# 01_MAIN.net
KiCad netlist of a schematic drawn in Altium Designer
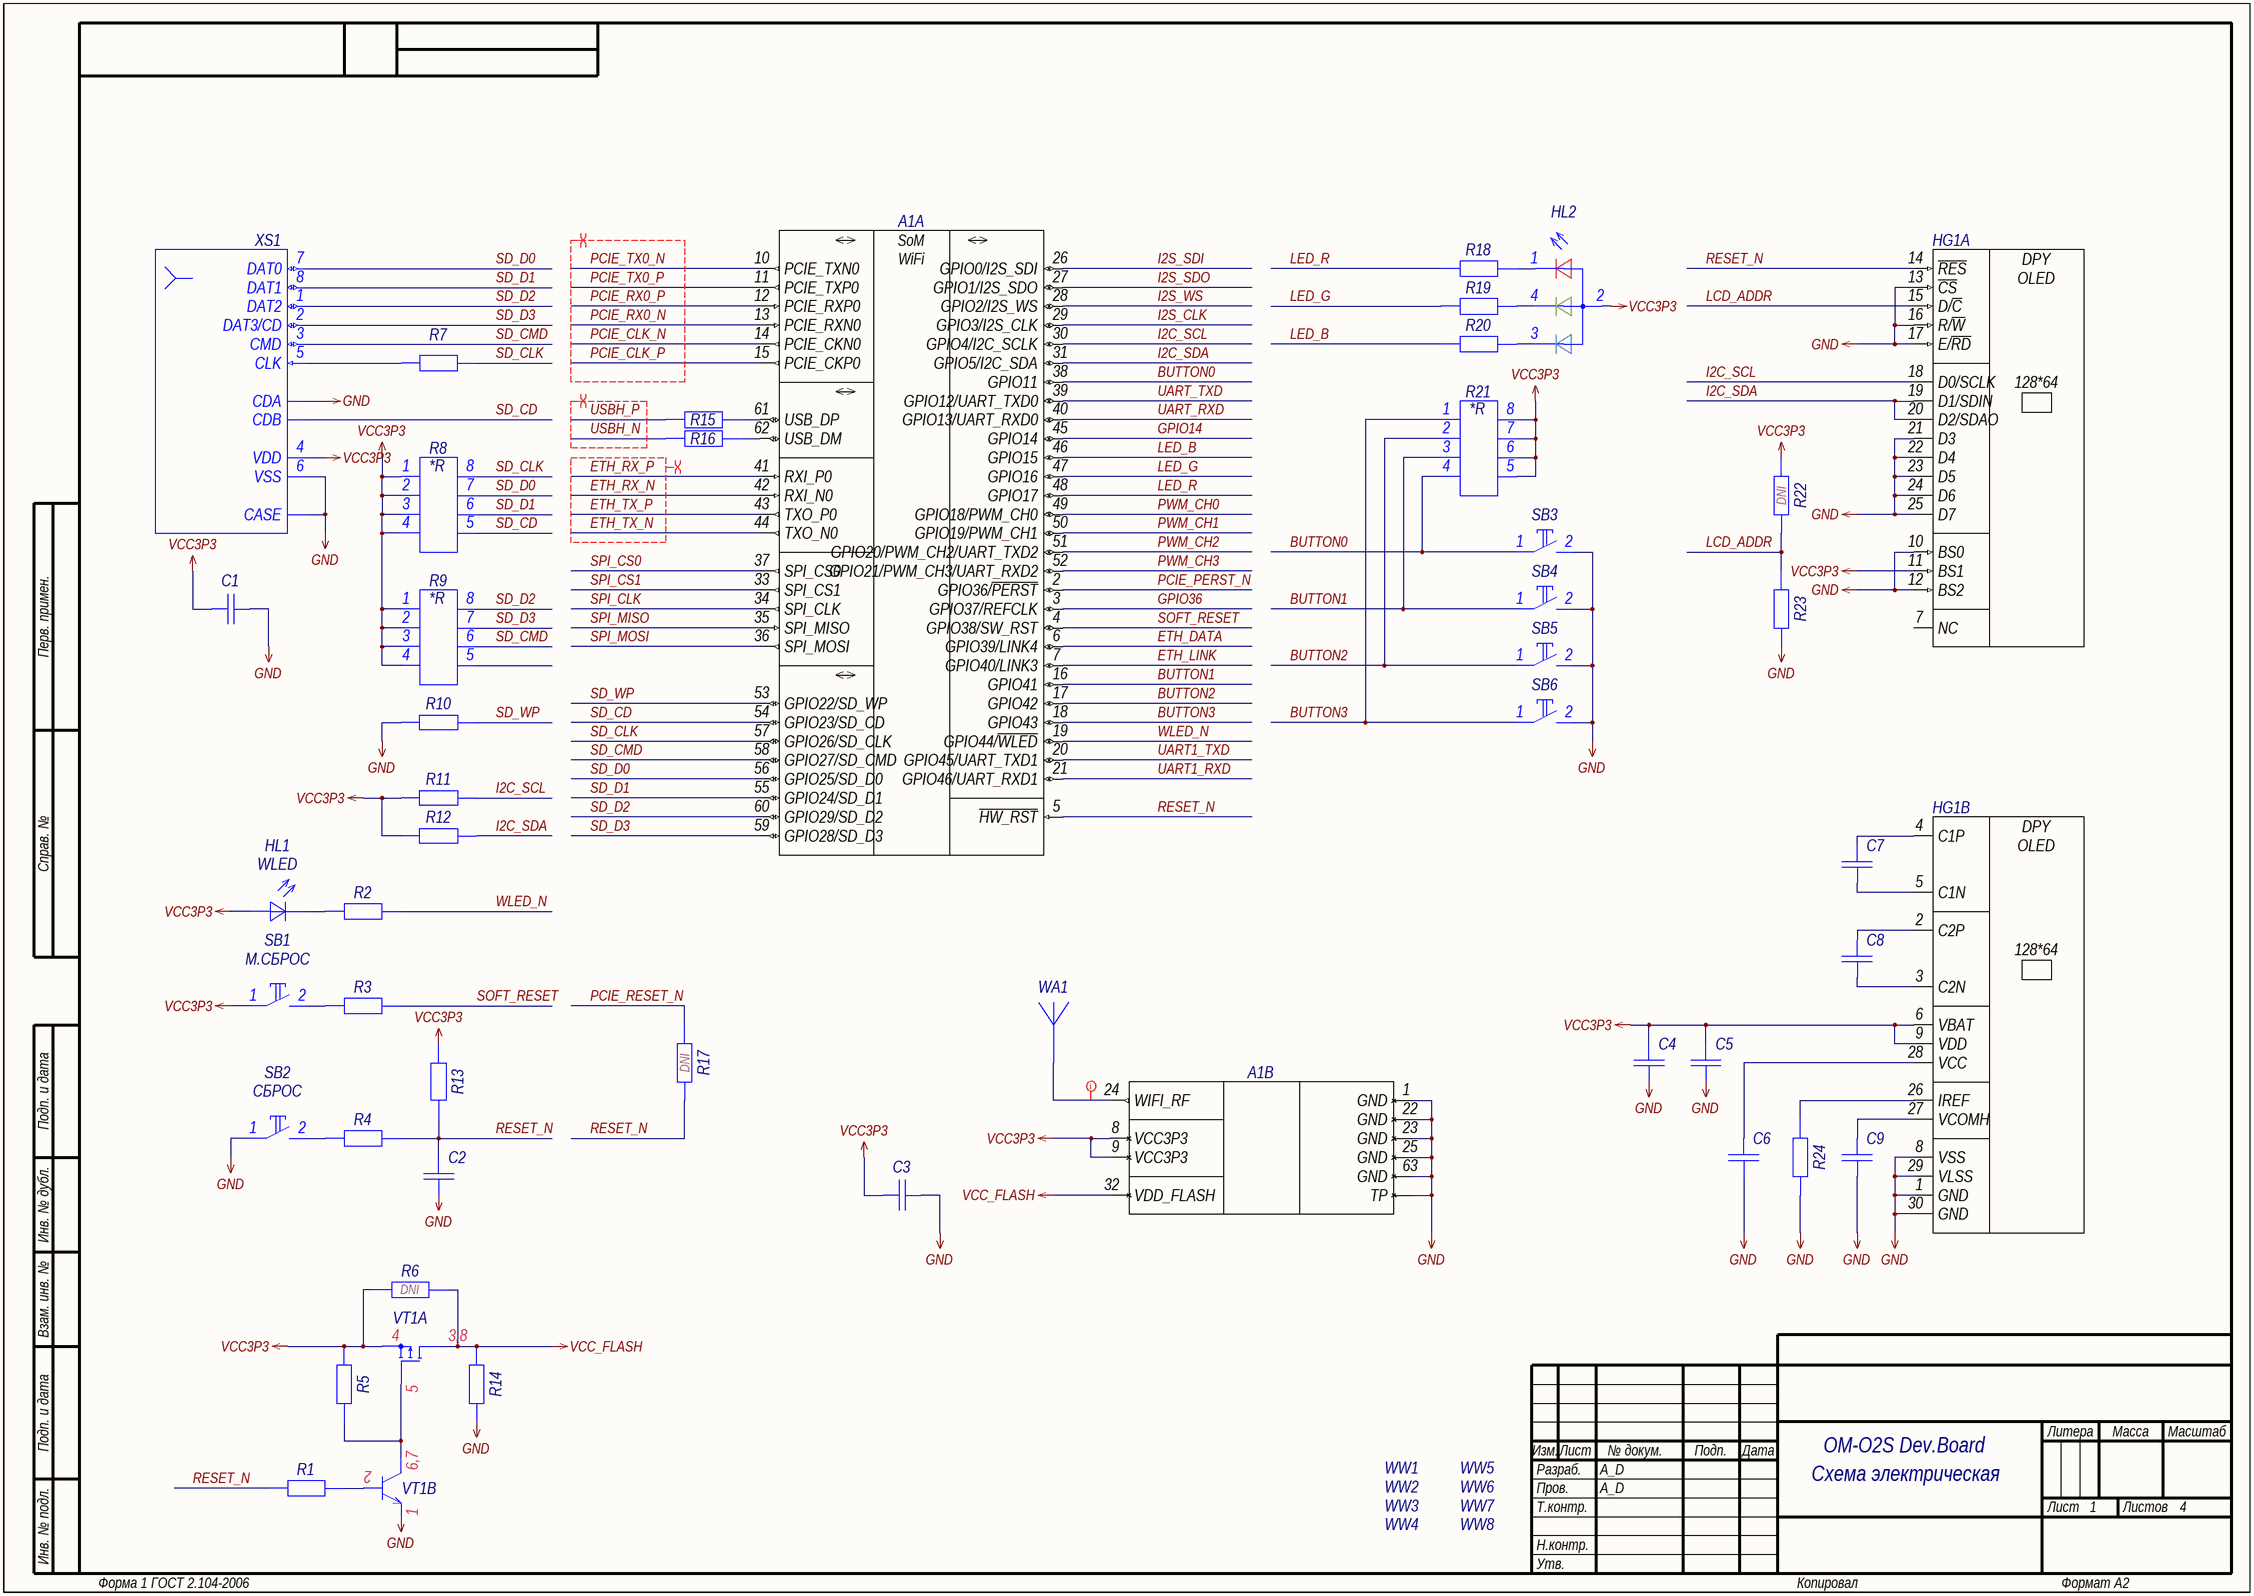
[diagram p0: 01_MAIN.SchDoc]

(export (version "E")
  (design (tool "Eeschema 10.0.6"))
  (components
    (comp (ref "A1")
      (value "OM-O2Sx")
      (footprint "OM-O2Sx")
      (fields
        (field (name "PART NUMBER") "OM-O2SP")
        (field (name "MANUFACTURER") "Onion")
        (field (name "PUBLISHER") "Andrew Danich")
      )
      (libsource (lib "ADLib") (part "OM-O2Sx"))
    )
    (comp (ref "C1")
      (value "Capacitor")
      (footprint "C0603_L")
      (fields
        (field (name "PART NUMBER") "GRM188R61A106KE69D")
        (field (name "VOLTAGE") "10V")
        (field (name "TOLERANCE") "±10%")
        (field (name "PUBLISHER") "Andrew Danich")
      )
      (libsource (lib "ADLib") (part "Capacitor"))
    )
    (comp (ref "C2")
      (value "Capacitor")
      (footprint "C0603_L")
      (fields
        (field (name "PART NUMBER") "GRM188R72A104KA35D")
        (field (name "VOLTAGE") "100V")
        (field (name "TOLERANCE") "±10%")
        (field (name "PUBLISHER") "Andrew Danich")
      )
      (libsource (lib "ADLib") (part "Capacitor"))
    )
    (comp (ref "C3")
      (value "Capacitor")
      (footprint "C0603_L")
      (fields
        (field (name "PART NUMBER") "GRM188R61A106KE69D")
        (field (name "VOLTAGE") "10V")
        (field (name "TOLERANCE") "±10%")
        (field (name "PUBLISHER") "Andrew Danich")
      )
      (libsource (lib "ADLib") (part "Capacitor"))
    )
    (comp (ref "C4")
      (value "Capacitor")
      (footprint "C0603_L")
      (fields
        (field (name "PART NUMBER") "GCM188R71E105KA64D")
        (field (name "VOLTAGE") "25V")
        (field (name "TOLERANCE") "±10%")
        (field (name "PUBLISHER") "Andrew Danich")
      )
      (libsource (lib "ADLib") (part "Capacitor"))
    )
    (comp (ref "C5")
      (value "Capacitor")
      (footprint "C0603_L")
      (fields
        (field (name "PART NUMBER") "GCM188R71E105KA64D")
        (field (name "VOLTAGE") "25V")
        (field (name "TOLERANCE") "±10%")
        (field (name "PUBLISHER") "Andrew Danich")
      )
      (libsource (lib "ADLib") (part "Capacitor"))
    )
    (comp (ref "C6")
      (value "Capacitor")
      (footprint "C0603_L")
      (fields
        (field (name "PART NUMBER") "GRM188R61E225MA12D")
        (field (name "VOLTAGE") "25V")
        (field (name "TOLERANCE") "±20%")
        (field (name "PUBLISHER") "Andrew Danich")
      )
      (libsource (lib "ADLib") (part "Capacitor"))
    )
    (comp (ref "C7")
      (value "Capacitor")
      (footprint "C0603_L")
      (fields
        (field (name "PART NUMBER") "GCM188R71E105KA64D")
        (field (name "VOLTAGE") "25V")
        (field (name "TOLERANCE") "±10%")
        (field (name "PUBLISHER") "Andrew Danich")
      )
      (libsource (lib "ADLib") (part "Capacitor"))
    )
    (comp (ref "C8")
      (value "Capacitor")
      (footprint "C0603_L")
      (fields
        (field (name "PART NUMBER") "GCM188R71E105KA64D")
        (field (name "VOLTAGE") "25V")
        (field (name "TOLERANCE") "±10%")
        (field (name "PUBLISHER") "Andrew Danich")
      )
      (libsource (lib "ADLib") (part "Capacitor"))
    )
    (comp (ref "C9")
      (value "Capacitor")
      (footprint "C0603_L")
      (fields
        (field (name "PART NUMBER") "GRT188C81E475KE13D")
        (field (name "VOLTAGE") "25V")
        (field (name "TOLERANCE") "±20%")
        (field (name "PUBLISHER") "Andrew Danich")
      )
      (libsource (lib "ADLib") (part "Capacitor"))
    )
    (comp (ref "HG1")
      (value "UG-2864HSWEG01")
      (footprint "UG-2864HSWEG01")
      (fields
        (field (name "MANUFACTURER") "WiseChip Semiconductor")
        (field (name "PUBLISHER") "Andrew Danich")
      )
      (libsource (lib "ADLib") (part "UG-2864HSWEG01"))
    )
    (comp (ref "HL1")
      (value "WLED")
      (footprint "LD0603_L")
      (fields (field (name "PART NUMBER") "BL-LS0603DNB") (field (name "PUBLISHER") "Andrew Danich"))
      (libsource (lib "ADLib") (part "Led-1"))
    )
    (comp (ref "HL2")
      (value "USER LED")
      (footprint "FM-B1515RGBA-HG")
      (fields
        (field (name "PART NUMBER") "FM-B1515RGBA-HG")
        (field (name "MANUFACTURER") "Foshan NationStar Optoelectronics")
        (field (name "PUBLISHER") "Andrew Danich")
      )
      (libsource (lib "ADLib") (part "FM-B1515RGBA-HG"))
    )
    (comp (ref "R1")
      (value "Resistor")
      (footprint "R0603_L")
      (fields
        (field (name "PART NUMBER") "RC0603JR-0722KL")
        (field (name "TOLERANCE") "±5%")
        (field (name "MANUFACTURER") "Yageo")
        (field (name "PUBLISHER") "Andrew Danich")
      )
      (libsource (lib "ADLib") (part "Resistor"))
    )
    (comp (ref "R2")
      (value "Resistor")
      (footprint "R0603_L")
      (fields
        (field (name "PART NUMBER") "RC0603JR-071KL")
        (field (name "TOLERANCE") "±5%")
        (field (name "MANUFACTURER") "Yageo")
        (field (name "PUBLISHER") "Andrew Danich")
      )
      (libsource (lib "ADLib") (part "Resistor"))
    )
    (comp (ref "R3")
      (value "Resistor")
      (footprint "R0603_L")
      (fields
        (field (name "PART NUMBER") "RC0603JR-073KL")
        (field (name "TOLERANCE") "±5%")
        (field (name "MANUFACTURER") "Yageo")
        (field (name "PUBLISHER") "Andrew Danich")
      )
      (libsource (lib "ADLib") (part "Resistor"))
    )
    (comp (ref "R4")
      (value "Resistor")
      (footprint "R0603_L")
      (fields
        (field (name "PART NUMBER") "RC0603JR-07100R")
        (field (name "TOLERANCE") "±5%")
        (field (name "MANUFACTURER") "Yageo")
        (field (name "PUBLISHER") "Andrew Danich")
      )
      (libsource (lib "ADLib") (part "Resistor"))
    )
    (comp (ref "R5")
      (value "Resistor")
      (footprint "R0603_L")
      (fields
        (field (name "PART NUMBER") "RC0603JR-0710KL")
        (field (name "TOLERANCE") "±5%")
        (field (name "MANUFACTURER") "Yageo")
        (field (name "PUBLISHER") "Andrew Danich")
      )
      (libsource (lib "ADLib") (part "Resistor"))
    )
    (comp (ref "R6")
      (value "Resistor")
      (footprint "R0603_L")
      (fields
        (field (name "PART NUMBER") "RC0603JR-070R")
        (field (name "TOLERANCE") "±5%")
        (field (name "MANUFACTURER") "Yageo")
        (field (name "PUBLISHER") "Andrew Danich")
      )
      (libsource (lib "ADLib") (part "Resistor"))
    )
    (comp (ref "R7")
      (value "Resistor")
      (footprint "R0603_L")
      (fields
        (field (name "PART NUMBER") "RC0603JR-0730RL")
        (field (name "TOLERANCE") "±5%")
        (field (name "MANUFACTURER") "Yageo")
        (field (name "PUBLISHER") "Andrew Danich")
      )
      (libsource (lib "ADLib") (part "Resistor"))
    )
    (comp (ref "R8")
      (value "Resistor-4")
      (footprint "CAT16-x4")
      (fields
        (field (name "PART NUMBER") "CAT16-103J4LF")
        (field (name "TOLERANCE") "±5%")
        (field (name "MANUFACTURER") "Bourns")
        (field (name "PUBLISHER") "Andrew Danich")
      )
      (libsource (lib "ADLib") (part "Resistor-4"))
    )
    (comp (ref "R9")
      (value "Resistor-4")
      (footprint "CAT16-x4")
      (fields
        (field (name "PART NUMBER") "CAT16-103J4LF")
        (field (name "TOLERANCE") "±5%")
        (field (name "MANUFACTURER") "Bourns")
        (field (name "PUBLISHER") "Andrew Danich")
      )
      (libsource (lib "ADLib") (part "Resistor-4"))
    )
    (comp (ref "R10")
      (value "Resistor")
      (footprint "R0603_L")
      (fields
        (field (name "PART NUMBER") "RC0603JR-074K7L")
        (field (name "TOLERANCE") "±5%")
        (field (name "MANUFACTURER") "Yageo")
        (field (name "PUBLISHER") "Andrew Danich")
      )
      (libsource (lib "ADLib") (part "Resistor"))
    )
    (comp (ref "R11")
      (value "Resistor")
      (footprint "R0603_L")
      (fields
        (field (name "PART NUMBER") "RC0603JR-074K7L")
        (field (name "TOLERANCE") "±5%")
        (field (name "MANUFACTURER") "Yageo")
        (field (name "PUBLISHER") "Andrew Danich")
      )
      (libsource (lib "ADLib") (part "Resistor"))
    )
    (comp (ref "R12")
      (value "Resistor")
      (footprint "R0603_L")
      (fields
        (field (name "PART NUMBER") "RC0603JR-074K7L")
        (field (name "TOLERANCE") "±5%")
        (field (name "MANUFACTURER") "Yageo")
        (field (name "PUBLISHER") "Andrew Danich")
      )
      (libsource (lib "ADLib") (part "Resistor"))
    )
    (comp (ref "R13")
      (value "Resistor")
      (footprint "R0603_L")
      (fields
        (field (name "PART NUMBER") "RC0603JR-074K7L")
        (field (name "TOLERANCE") "±5%")
        (field (name "MANUFACTURER") "Yageo")
        (field (name "PUBLISHER") "Andrew Danich")
      )
      (libsource (lib "ADLib") (part "Resistor"))
    )
    (comp (ref "R14")
      (value "Resistor")
      (footprint "R0603_L")
      (fields
        (field (name "PART NUMBER") "RC0603JR-073KL")
        (field (name "TOLERANCE") "±5%")
        (field (name "MANUFACTURER") "Yageo")
        (field (name "PUBLISHER") "Andrew Danich")
      )
      (libsource (lib "ADLib") (part "Resistor"))
    )
    (comp (ref "R15")
      (value "Resistor")
      (footprint "R0603_L")
      (fields
        (field (name "PART NUMBER") "RC0603JR-0722RL")
        (field (name "TOLERANCE") "±5%")
        (field (name "MANUFACTURER") "Yageo")
        (field (name "PUBLISHER") "Andrew Danich")
      )
      (libsource (lib "ADLib") (part "Resistor"))
    )
    (comp (ref "R16")
      (value "Resistor")
      (footprint "R0603_L")
      (fields
        (field (name "PART NUMBER") "RC0603JR-0722RL")
        (field (name "TOLERANCE") "±5%")
        (field (name "MANUFACTURER") "Yageo")
        (field (name "PUBLISHER") "Andrew Danich")
      )
      (libsource (lib "ADLib") (part "Resistor"))
    )
    (comp (ref "R17")
      (value "Resistor")
      (footprint "R0603_L")
      (fields
        (field (name "PART NUMBER") "RC0603JR-070R")
        (field (name "TOLERANCE") "±5%")
        (field (name "MANUFACTURER") "Yageo")
        (field (name "PUBLISHER") "Andrew Danich")
      )
      (libsource (lib "ADLib") (part "Resistor"))
    )
    (comp (ref "R18")
      (value "Resistor")
      (footprint "R0603_L")
      (fields
        (field (name "PART NUMBER") "RC0603JR-07100R")
        (field (name "TOLERANCE") "±5%")
        (field (name "MANUFACTURER") "Yageo")
        (field (name "PUBLISHER") "Andrew Danich")
      )
      (libsource (lib "ADLib") (part "Resistor"))
    )
    (comp (ref "R19")
      (value "Resistor")
      (footprint "R0603_L")
      (fields
        (field (name "PART NUMBER") "RC0603JR-07100R")
        (field (name "TOLERANCE") "±5%")
        (field (name "MANUFACTURER") "Yageo")
        (field (name "PUBLISHER") "Andrew Danich")
      )
      (libsource (lib "ADLib") (part "Resistor"))
    )
    (comp (ref "R20")
      (value "Resistor")
      (footprint "R0603_L")
      (fields
        (field (name "PART NUMBER") "RC0603JR-07100R")
        (field (name "TOLERANCE") "±5%")
        (field (name "MANUFACTURER") "Yageo")
        (field (name "PUBLISHER") "Andrew Danich")
      )
      (libsource (lib "ADLib") (part "Resistor"))
    )
    (comp (ref "R21")
      (value "Resistor-4")
      (footprint "CAT16-x4")
      (fields
        (field (name "PART NUMBER") "CAT16-103J4LF")
        (field (name "TOLERANCE") "±5%")
        (field (name "MANUFACTURER") "Bourns")
        (field (name "PUBLISHER") "Andrew Danich")
      )
      (libsource (lib "ADLib") (part "Resistor-4"))
    )
    (comp (ref "R22")
      (value "Resistor")
      (footprint "R0603_L")
      (fields
        (field (name "PART NUMBER") "RC0603JR-070R")
        (field (name "TOLERANCE") "±5%")
        (field (name "MANUFACTURER") "Yageo")
        (field (name "PUBLISHER") "Andrew Danich")
      )
      (libsource (lib "ADLib") (part "Resistor"))
    )
    (comp (ref "R23")
      (value "Resistor")
      (footprint "R0603_L")
      (fields
        (field (name "PART NUMBER") "RC0603JR-070R")
        (field (name "TOLERANCE") "±5%")
        (field (name "MANUFACTURER") "Yageo")
        (field (name "PUBLISHER") "Andrew Danich")
      )
      (libsource (lib "ADLib") (part "Resistor"))
    )
    (comp (ref "R24")
      (value "Resistor")
      (footprint "R0603_L")
      (fields
        (field (name "PART NUMBER") "RC0603JR-07910KL")
        (field (name "TOLERANCE") "±5%")
        (field (name "MANUFACTURER") "Yageo")
        (field (name "PUBLISHER") "Andrew Danich")
      )
      (libsource (lib "ADLib") (part "Resistor"))
    )
    (comp (ref "SB1")
      (value "М.СБРОС")
      (footprint "IT-1185AP")
      (fields (field (name "PART NUMBER") "IT-1185AP") (field (name "PUBLISHER") "Andrew Danich"))
      (libsource (lib "ADLib") (part "BT-01x-01p"))
    )
    (comp (ref "SB2")
      (value "СБРОС")
      (footprint "IT-1185AP")
      (fields (field (name "PART NUMBER") "IT-1185AP") (field (name "PUBLISHER") "Andrew Danich"))
      (libsource (lib "ADLib") (part "BT-01x-01p"))
    )
    (comp (ref "SB3")
      (value "~")
      (footprint "IT-1185AP")
      (fields (field (name "PART NUMBER") "IT-1185AP") (field (name "PUBLISHER") "Andrew Danich"))
      (libsource (lib "ADLib") (part "BT-01x-01p"))
    )
    (comp (ref "SB4")
      (value "~")
      (footprint "IT-1185AP")
      (fields (field (name "PART NUMBER") "IT-1185AP") (field (name "PUBLISHER") "Andrew Danich"))
      (libsource (lib "ADLib") (part "BT-01x-01p"))
    )
    (comp (ref "SB5")
      (value "~")
      (footprint "IT-1185AP")
      (fields (field (name "PART NUMBER") "IT-1185AP") (field (name "PUBLISHER") "Andrew Danich"))
      (libsource (lib "ADLib") (part "BT-01x-01p"))
    )
    (comp (ref "SB6")
      (value "~")
      (footprint "IT-1185AP")
      (fields (field (name "PART NUMBER") "IT-1185AP") (field (name "PUBLISHER") "Andrew Danich"))
      (libsource (lib "ADLib") (part "BT-01x-01p"))
    )
    (comp (ref "VT1")
      (value "PMC85XP")
      (footprint "SOT-1118-2M_065P200X200X065_N")
      (fields (field (name "MANUFACTURER") "NXP Semiconductors") (field (name "PUBLISHER") "Andrew Danich"))
      (libsource (lib "") (part "PMC85XP_1"))
    )
    (comp (ref "WA1")
      (value "Antenna_US_1p")
      (footprint "AN9520")
      (fields
        (field (name "PART NUMBER") "AN9520")
        (field (name "MANUFACTURER") "RainSun")
        (field (name "PUBLISHER") "Andrew Danich")
      )
      (libsource (lib "ADLib") (part "Antenna_US_1p"))
    )
    (comp (ref "WW1")
      (value "NoBody")
      (footprint "MH_M2.5")
      (fields (field (name "PART NUMBER") "MOUNTINGHOLE") (field (name "PUBLISHER") "Andrew Danich"))
      (libsource (lib "ADLib") (part "NoBody"))
    )
    (comp (ref "WW2")
      (value "NoBody")
      (footprint "MH_M2.5")
      (fields (field (name "PART NUMBER") "MOUNTINGHOLE") (field (name "PUBLISHER") "Andrew Danich"))
      (libsource (lib "ADLib") (part "NoBody"))
    )
    (comp (ref "WW3")
      (value "NoBody")
      (footprint "MH_M2.5")
      (fields (field (name "PART NUMBER") "MOUNTINGHOLE") (field (name "PUBLISHER") "Andrew Danich"))
      (libsource (lib "ADLib") (part "NoBody"))
    )
    (comp (ref "WW4")
      (value "NoBody")
      (footprint "MH_M2.5")
      (fields (field (name "PART NUMBER") "MOUNTINGHOLE") (field (name "PUBLISHER") "Andrew Danich"))
      (libsource (lib "ADLib") (part "NoBody"))
    )
    (comp (ref "WW5")
      (value "NoBody")
      (footprint "MH_M3.0")
      (fields (field (name "PART NUMBER") "MOUNTINGHOLE") (field (name "PUBLISHER") "Andrew Danich"))
      (libsource (lib "ADLib") (part "NoBody"))
    )
    (comp (ref "WW6")
      (value "NoBody")
      (footprint "MH_M3.0")
      (fields (field (name "PART NUMBER") "MOUNTINGHOLE") (field (name "PUBLISHER") "Andrew Danich"))
      (libsource (lib "ADLib") (part "NoBody"))
    )
    (comp (ref "WW7")
      (value "NoBody")
      (footprint "MH_M3.0")
      (fields (field (name "PART NUMBER") "MOUNTINGHOLE") (field (name "PUBLISHER") "Andrew Danich"))
      (libsource (lib "ADLib") (part "NoBody"))
    )
    (comp (ref "WW8")
      (value "NoBody")
      (footprint "MH_M3.0")
      (fields (field (name "PART NUMBER") "MOUNTINGHOLE") (field (name "PUBLISHER") "Andrew Danich"))
      (libsource (lib "ADLib") (part "NoBody"))
    )
    (comp (ref "XS1")
      (value "DM3AT-SF-PEJM5")
      (footprint "DM3AT-SF-PEJM5")
      (fields (field (name "MANUFACTURER") "Hirose Connector") (field (name "PUBLISHER") "Andrew Danich"))
      (libsource (lib "ADLib") (part "DM3AT-SF-PEJM5"))
    )
  )
  (nets
    (net (code "1") (name "/BUTTON0") (class "Default")
      (node (ref "A1") (pin "38") (pinfunction "GPIO11_38") (pintype "bidirectional"))
      (node (ref "R21") (pin "4") (pintype "passive"))
      (node (ref "SB3") (pin "1") (pintype "passive"))
    )
    (net (code "2") (name "/BUTTON1") (class "Default")
      (node (ref "A1") (pin "16") (pinfunction "GPIO41_16") (pintype "bidirectional"))
      (node (ref "R21") (pin "3") (pintype "passive"))
      (node (ref "SB4") (pin "1") (pintype "passive"))
    )
    (net (code "3") (name "/BUTTON2") (class "Default")
      (node (ref "A1") (pin "17") (pinfunction "GPIO42_17") (pintype "bidirectional"))
      (node (ref "R21") (pin "2") (pintype "passive"))
      (node (ref "SB5") (pin "1") (pintype "passive"))
    )
    (net (code "4") (name "/BUTTON3") (class "Default")
      (node (ref "A1") (pin "18") (pinfunction "GPIO43_18") (pintype "bidirectional"))
      (node (ref "R21") (pin "1") (pintype "passive"))
      (node (ref "SB6") (pin "1") (pintype "passive"))
    )
    (net (code "5") (name "/ETH_DATA") (class "Default")
      (node (ref "A1") (pin "6") (pinfunction "GPIO39/LINK4_6") (pintype "bidirectional"))
    )
    (net (code "6") (name "/ETH_LINK") (class "Default")
      (node (ref "A1") (pin "7") (pinfunction "GPIO40/LINK3_7") (pintype "bidirectional"))
    )
    (net (code "7") (name "/ETH_RX_N") (class "Default")
      (node (ref "A1") (pin "42") (pinfunction "RXI_N0_42") (pintype "input"))
    )
    (net (code "8") (name "/ETH_RX_P") (class "Default")
      (node (ref "A1") (pin "41") (pinfunction "RXI_P0_41") (pintype "input"))
    )
    (net (code "9") (name "/ETH_TX_N") (class "Default")
      (node (ref "A1") (pin "44") (pinfunction "TXO_N0_44") (pintype "output"))
    )
    (net (code "10") (name "/ETH_TX_P") (class "Default")
      (node (ref "A1") (pin "43") (pinfunction "TXO_P0_43") (pintype "output"))
    )
    (net (code "11") (name "/GPIO14") (class "Default")
      (node (ref "A1") (pin "45") (pinfunction "GPIO14_45") (pintype "bidirectional"))
    )
    (net (code "12") (name "/GPIO36") (class "Default")
      (node (ref "A1") (pin "3") (pinfunction "GPIO37/REFCLK_3") (pintype "bidirectional"))
    )
    (net (code "13") (name "/I2C_SCL") (class "Default")
      (node (ref "A1") (pin "30") (pinfunction "GPIO4/I2C_SCLK_30") (pintype "bidirectional"))
      (node (ref "HG1") (pin "18") (pinfunction "D0/SCLK_18") (pintype "passive"))
      (node (ref "R11") (pin "2") (pinfunction "2_2") (pintype "passive"))
    )
    (net (code "14") (name "/I2C_SDA") (class "Default")
      (node (ref "A1") (pin "31") (pinfunction "GPIO5/I2C_SDA_31") (pintype "bidirectional"))
      (node (ref "HG1") (pin "19") (pinfunction "D1/SDIN_19") (pintype "passive"))
      (node (ref "HG1") (pin "20") (pinfunction "D2/SDAO_20") (pintype "passive"))
      (node (ref "R12") (pin "2") (pinfunction "2_2") (pintype "passive"))
    )
    (net (code "15") (name "/I2S_CLK") (class "Default")
      (node (ref "A1") (pin "29") (pinfunction "GPIO3/I2S_CLK_29") (pintype "bidirectional"))
    )
    (net (code "16") (name "/I2S_SDI") (class "Default")
      (node (ref "A1") (pin "26") (pinfunction "GPIO0/I2S_SDI_26") (pintype "bidirectional"))
    )
    (net (code "17") (name "/I2S_SDO") (class "Default")
      (node (ref "A1") (pin "27") (pinfunction "GPIO1/I2S_SDO_27") (pintype "bidirectional"))
    )
    (net (code "18") (name "/I2S_WS") (class "Default")
      (node (ref "A1") (pin "28") (pinfunction "GPIO2/I2S_WS_28") (pintype "bidirectional"))
    )
    (net (code "19") (name "/LCD_ADDR") (class "Default")
      (node (ref "HG1") (pin "15") (pinfunction "D/~{C}_15") (pintype "input"))
      (node (ref "R22") (pin "1") (pinfunction "1_1") (pintype "passive"))
      (node (ref "R23") (pin "2") (pinfunction "2_2") (pintype "passive"))
    )
    (net (code "20") (name "/LED_B") (class "Default")
      (node (ref "A1") (pin "46") (pinfunction "GPIO15_46") (pintype "bidirectional"))
      (node (ref "R20") (pin "1") (pinfunction "1_1") (pintype "passive"))
    )
    (net (code "21") (name "/LED_G") (class "Default")
      (node (ref "A1") (pin "47") (pinfunction "GPIO16_47") (pintype "bidirectional"))
      (node (ref "R19") (pin "1") (pinfunction "1_1") (pintype "passive"))
    )
    (net (code "22") (name "/LED_R") (class "Default")
      (node (ref "A1") (pin "48") (pinfunction "GPIO17_48") (pintype "bidirectional"))
      (node (ref "R18") (pin "1") (pinfunction "1_1") (pintype "passive"))
    )
    (net (code "23") (name "/PCIE_CLK_N") (class "Default")
      (node (ref "A1") (pin "14") (pinfunction "PCIE_CKN0_14") (pintype "output"))
    )
    (net (code "24") (name "/PCIE_CLK_P") (class "Default")
      (node (ref "A1") (pin "15") (pinfunction "PCIE_CKP0_15") (pintype "output"))
    )
    (net (code "25") (name "/PCIE_PERST_N") (class "Default")
      (node (ref "A1") (pin "2") (pinfunction "GPIO36/~{PERST}_2") (pintype "bidirectional"))
    )
    (net (code "26") (name "/PCIE_RESET_N") (class "Default")
      (node (ref "R17") (pin "1") (pinfunction "1_1") (pintype "passive"))
    )
    (net (code "27") (name "/PCIE_RX0_N") (class "Default")
      (node (ref "A1") (pin "13") (pinfunction "PCIE_RXN0_13") (pintype "input"))
    )
    (net (code "28") (name "/PCIE_RX0_P") (class "Default")
      (node (ref "A1") (pin "12") (pinfunction "PCIE_RXP0_12") (pintype "input"))
    )
    (net (code "29") (name "/PCIE_TX0_N") (class "Default")
      (node (ref "A1") (pin "10") (pinfunction "PCIE_TXN0_10") (pintype "output"))
    )
    (net (code "30") (name "/PCIE_TX0_P") (class "Default")
      (node (ref "A1") (pin "11") (pinfunction "PCIE_TXP0_11") (pintype "output"))
    )
    (net (code "31") (name "/PWM_CH0") (class "Default")
      (node (ref "A1") (pin "49") (pinfunction "GPIO18/PWM_CH0_49") (pintype "bidirectional"))
    )
    (net (code "32") (name "/PWM_CH1") (class "Default")
      (node (ref "A1") (pin "50") (pinfunction "GPIO19/PWM_CH1_50") (pintype "bidirectional"))
    )
    (net (code "33") (name "/PWM_CH2") (class "Default")
      (node (ref "A1") (pin "51") (pinfunction "GPIO20/PWM_CH2/UART_TXD2_51") (pintype "bidirectional"))
    )
    (net (code "34") (name "/PWM_CH3") (class "Default")
      (node (ref "A1") (pin "52") (pinfunction "GPIO21/PWM_CH3/UART_RXD2_52") (pintype "bidirectional"))
    )
    (net (code "35") (name "/RESET_N") (class "Default")
      (node (ref "A1") (pin "5") (pinfunction "~{HW_RST}_5") (pintype "input"))
      (node (ref "C2") (pin "2") (pinfunction "2_2") (pintype "passive"))
      (node (ref "HG1") (pin "14") (pinfunction "~{RES}_14") (pintype "input"))
      (node (ref "R1") (pin "1") (pinfunction "1_1") (pintype "passive"))
      (node (ref "R13") (pin "1") (pinfunction "1_1") (pintype "passive"))
      (node (ref "R17") (pin "2") (pinfunction "2_2") (pintype "passive"))
      (node (ref "R4") (pin "2") (pinfunction "2_2") (pintype "passive"))
    )
    (net (code "36") (name "/SD_CD") (class "Default")
      (node (ref "A1") (pin "54") (pinfunction "GPIO23/SD_CD_54") (pintype "bidirectional"))
      (node (ref "R8") (pin "5") (pintype "passive"))
      (node (ref "XS1") (pin "CDB") (pinfunction "CDB_CDB") (pintype "passive"))
    )
    (net (code "37") (name "/SD_CLK") (class "Default")
      (node (ref "A1") (pin "57") (pinfunction "GPIO26/SD_CLK_57") (pintype "bidirectional"))
      (node (ref "R7") (pin "2") (pinfunction "2_2") (pintype "passive"))
      (node (ref "R8") (pin "8") (pintype "passive"))
    )
    (net (code "38") (name "/SD_CMD") (class "Default")
      (node (ref "A1") (pin "58") (pinfunction "GPIO27/SD_CMD_58") (pintype "bidirectional"))
      (node (ref "R9") (pin "6") (pintype "passive"))
      (node (ref "XS1") (pin "3") (pinfunction "CMD_3") (pintype "bidirectional"))
    )
    (net (code "39") (name "/SD_D0") (class "Default")
      (node (ref "A1") (pin "56") (pinfunction "GPIO25/SD_D0_56") (pintype "bidirectional"))
      (node (ref "R8") (pin "7") (pintype "passive"))
      (node (ref "XS1") (pin "7") (pinfunction "DAT0_7") (pintype "bidirectional"))
    )
    (net (code "40") (name "/SD_D1") (class "Default")
      (node (ref "A1") (pin "55") (pinfunction "GPIO24/SD_D1_55") (pintype "bidirectional"))
      (node (ref "R8") (pin "6") (pintype "passive"))
      (node (ref "XS1") (pin "8") (pinfunction "DAT1_8") (pintype "bidirectional"))
    )
    (net (code "41") (name "/SD_D2") (class "Default")
      (node (ref "A1") (pin "60") (pinfunction "GPIO29/SD_D2_60") (pintype "bidirectional"))
      (node (ref "R9") (pin "8") (pintype "passive"))
      (node (ref "XS1") (pin "1") (pinfunction "DAT2_1") (pintype "bidirectional"))
    )
    (net (code "42") (name "/SD_D3") (class "Default")
      (node (ref "A1") (pin "59") (pinfunction "GPIO28/SD_D3_59") (pintype "bidirectional"))
      (node (ref "R9") (pin "7") (pintype "passive"))
      (node (ref "XS1") (pin "2") (pinfunction "DAT3/CD_2") (pintype "bidirectional"))
    )
    (net (code "43") (name "/SD_WP") (class "Default")
      (node (ref "A1") (pin "53") (pinfunction "GPIO22/SD_WP_53") (pintype "bidirectional"))
      (node (ref "R10") (pin "2") (pinfunction "2_2") (pintype "passive"))
    )
    (net (code "44") (name "/SOFT_RESET") (class "Default")
      (node (ref "A1") (pin "4") (pinfunction "GPIO38/SW_RST_4") (pintype "bidirectional"))
      (node (ref "R3") (pin "2") (pinfunction "2_2") (pintype "passive"))
    )
    (net (code "45") (name "/SPI_CLK") (class "Default")
      (node (ref "A1") (pin "34") (pinfunction "SPI_CLK_34") (pintype "output"))
    )
    (net (code "46") (name "/SPI_CS0") (class "Default")
      (node (ref "A1") (pin "37") (pinfunction "SPI_CS0_37") (pintype "output"))
    )
    (net (code "47") (name "/SPI_CS1") (class "Default")
      (node (ref "A1") (pin "33") (pinfunction "SPI_CS1_33") (pintype "output"))
    )
    (net (code "48") (name "/SPI_MISO") (class "Default")
      (node (ref "A1") (pin "35") (pinfunction "SPI_MISO_35") (pintype "input"))
    )
    (net (code "49") (name "/SPI_MOSI") (class "Default")
      (node (ref "A1") (pin "36") (pinfunction "SPI_MOSI_36") (pintype "output"))
    )
    (net (code "50") (name "/UART1_RXD") (class "Default")
      (node (ref "A1") (pin "21") (pinfunction "GPIO46/UART_RXD1_21") (pintype "bidirectional"))
    )
    (net (code "51") (name "/UART1_TXD") (class "Default")
      (node (ref "A1") (pin "20") (pinfunction "GPIO45/UART_TXD1_20") (pintype "bidirectional"))
    )
    (net (code "52") (name "/UART_RXD") (class "Default")
      (node (ref "A1") (pin "40") (pinfunction "GPIO13/UART_RXD0_40") (pintype "bidirectional"))
    )
    (net (code "53") (name "/UART_TXD") (class "Default")
      (node (ref "A1") (pin "39") (pinfunction "GPIO12/UART_TXD0_39") (pintype "bidirectional"))
    )
    (net (code "54") (name "/USBH_N") (class "Default")
      (node (ref "R16") (pin "1") (pinfunction "1_1") (pintype "passive"))
    )
    (net (code "55") (name "/USBH_P") (class "Default")
      (node (ref "R15") (pin "1") (pinfunction "1_1") (pintype "passive"))
    )
    (net (code "56") (name "/WLED_N") (class "Default")
      (node (ref "A1") (pin "19") (pinfunction "GPIO44/~{WLED}_19") (pintype "bidirectional"))
      (node (ref "R2") (pin "2") (pinfunction "2_2") (pintype "passive"))
    )
    (net (code "57") (name "GND") (class "Default")
      (node (ref "A1") (pin "1") (pinfunction "GND_1") (pintype "power_in"))
      (node (ref "A1") (pin "22") (pinfunction "GND_22") (pintype "power_in"))
      (node (ref "A1") (pin "23") (pinfunction "GND_23") (pintype "power_in"))
      (node (ref "A1") (pin "25") (pinfunction "GND_25") (pintype "power_in"))
      (node (ref "A1") (pin "63") (pinfunction "GND_63") (pintype "power_in"))
      (node (ref "A1") (pin "TP") (pinfunction "TP_TP") (pintype "power_in"))
      (node (ref "C1") (pin "2") (pinfunction "2_2") (pintype "passive"))
      (node (ref "C2") (pin "1") (pinfunction "1_1") (pintype "passive"))
      (node (ref "C3") (pin "2") (pinfunction "2_2") (pintype "passive"))
      (node (ref "C4") (pin "1") (pinfunction "1_1") (pintype "passive"))
      (node (ref "C5") (pin "1") (pinfunction "1_1") (pintype "passive"))
      (node (ref "C6") (pin "1") (pinfunction "1_1") (pintype "passive"))
      (node (ref "C9") (pin "1") (pinfunction "1_1") (pintype "passive"))
      (node (ref "HG1") (pin "1") (pinfunction "GND_1") (pintype "passive"))
      (node (ref "HG1") (pin "10") (pinfunction "BS0_10") (pintype "input"))
      (node (ref "HG1") (pin "12") (pinfunction "BS2_12") (pintype "input"))
      (node (ref "HG1") (pin "13") (pinfunction "~{CS}_13") (pintype "input"))
      (node (ref "HG1") (pin "16") (pinfunction "R/~{W}_16") (pintype "input"))
      (node (ref "HG1") (pin "17") (pinfunction "E/~{RD}_17") (pintype "input"))
      (node (ref "HG1") (pin "21") (pinfunction "D3_21") (pintype "passive"))
      (node (ref "HG1") (pin "22") (pinfunction "D4_22") (pintype "passive"))
      (node (ref "HG1") (pin "23") (pinfunction "D5_23") (pintype "passive"))
      (node (ref "HG1") (pin "24") (pinfunction "D6_24") (pintype "passive"))
      (node (ref "HG1") (pin "25") (pinfunction "D7_25") (pintype "passive"))
      (node (ref "HG1") (pin "29") (pinfunction "VLSS_29") (pintype "power_in"))
      (node (ref "HG1") (pin "30") (pinfunction "GND_30") (pintype "passive"))
      (node (ref "HG1") (pin "8") (pinfunction "VSS_8") (pintype "power_in"))
      (node (ref "R10") (pin "1") (pinfunction "1_1") (pintype "passive"))
      (node (ref "R14") (pin "1") (pinfunction "1_1") (pintype "passive"))
      (node (ref "R23") (pin "1") (pinfunction "1_1") (pintype "passive"))
      (node (ref "R24") (pin "1") (pinfunction "1_1") (pintype "passive"))
      (node (ref "SB2") (pin "1") (pintype "passive"))
      (node (ref "SB3") (pin "2") (pintype "passive"))
      (node (ref "SB4") (pin "2") (pintype "passive"))
      (node (ref "SB5") (pin "2") (pintype "passive"))
      (node (ref "SB6") (pin "2") (pintype "passive"))
      (node (ref "VT1") (pin "1") (pinfunction "Э_1") (pintype "passive"))
      (node (ref "XS1") (pin "6") (pinfunction "VSS_6") (pintype "power_in"))
      (node (ref "XS1") (pin "CASE") (pinfunction "CASE_CASE") (pintype "passive"))
      (node (ref "XS1") (pin "CDA") (pinfunction "CDA_CDA") (pintype "passive"))
    )
    (net (code "58") (name "Net-(A1A-USB_DM)") (class "Default")
      (node (ref "A1") (pin "62") (pinfunction "USB_DM_62") (pintype "bidirectional"))
      (node (ref "R16") (pin "2") (pinfunction "2_2") (pintype "passive"))
    )
    (net (code "59") (name "Net-(A1A-USB_DP)") (class "Default")
      (node (ref "A1") (pin "61") (pinfunction "USB_DP_61") (pintype "bidirectional"))
      (node (ref "R15") (pin "2") (pinfunction "2_2") (pintype "passive"))
    )
    (net (code "60") (name "Net-(A1B-WIFI_RF)") (class "Default")
      (node (ref "A1") (pin "24") (pinfunction "WIFI_RF_24") (pintype "output"))
      (node (ref "WA1") (pin "1") (pinfunction "1_1") (pintype "passive"))
    )
    (net (code "61") (name "Net-(HG1B-C1N)") (class "Default")
      (node (ref "C7") (pin "1") (pinfunction "1_1") (pintype "passive"))
      (node (ref "HG1") (pin "5") (pinfunction "C1N_5") (pintype "passive"))
    )
    (net (code "62") (name "Net-(HG1B-C1P)") (class "Default")
      (node (ref "C7") (pin "2") (pinfunction "2_2") (pintype "passive"))
      (node (ref "HG1") (pin "4") (pinfunction "C1P_4") (pintype "passive"))
    )
    (net (code "63") (name "Net-(HG1B-C2N)") (class "Default")
      (node (ref "C8") (pin "1") (pinfunction "1_1") (pintype "passive"))
      (node (ref "HG1") (pin "3") (pinfunction "C2N_3") (pintype "passive"))
    )
    (net (code "64") (name "Net-(HG1B-C2P)") (class "Default")
      (node (ref "C8") (pin "2") (pinfunction "2_2") (pintype "passive"))
      (node (ref "HG1") (pin "2") (pinfunction "C2P_2") (pintype "passive"))
    )
    (net (code "65") (name "Net-(HG1B-IREF)") (class "Default")
      (node (ref "HG1") (pin "26") (pinfunction "IREF_26") (pintype "passive"))
      (node (ref "R24") (pin "2") (pinfunction "2_2") (pintype "passive"))
    )
    (net (code "66") (name "Net-(HG1B-VCC)") (class "Default")
      (node (ref "C6") (pin "2") (pinfunction "2_2") (pintype "passive"))
      (node (ref "HG1") (pin "28") (pinfunction "VCC_28") (pintype "power_in"))
    )
    (net (code "67") (name "Net-(HG1B-VCOMH)") (class "Default")
      (node (ref "C9") (pin "2") (pinfunction "2_2") (pintype "passive"))
      (node (ref "HG1") (pin "27") (pinfunction "VCOMH_27") (pintype "passive"))
    )
    (net (code "68") (name "Net-(HL1-К)") (class "Default")
      (node (ref "HL1") (pin "2") (pinfunction "К_2") (pintype "passive"))
      (node (ref "R2") (pin "1") (pinfunction "1_1") (pintype "passive"))
    )
    (net (code "69") (name "Net-(HL2-Pad1)") (class "Default")
      (node (ref "HL2") (pin "1") (pinfunction "1_1") (pintype "passive"))
      (node (ref "R18") (pin "2") (pinfunction "2_2") (pintype "passive"))
    )
    (net (code "70") (name "Net-(HL2-Pad3)") (class "Default")
      (node (ref "HL2") (pin "3") (pinfunction "3_3") (pintype "passive"))
      (node (ref "R20") (pin "2") (pinfunction "2_2") (pintype "passive"))
    )
    (net (code "71") (name "Net-(HL2-Pad4)") (class "Default")
      (node (ref "HL2") (pin "4") (pinfunction "4_4") (pintype "passive"))
      (node (ref "R19") (pin "2") (pinfunction "2_2") (pintype "passive"))
    )
    (net (code "72") (name "Net-(R3-Pad1)") (class "Default")
      (node (ref "R3") (pin "1") (pinfunction "1_1") (pintype "passive"))
      (node (ref "SB1") (pin "2") (pintype "passive"))
    )
    (net (code "73") (name "Net-(R4-Pad1)") (class "Default")
      (node (ref "R4") (pin "1") (pinfunction "1_1") (pintype "passive"))
      (node (ref "SB2") (pin "2") (pintype "passive"))
    )
    (net (code "74") (name "Net-(VT1A-G)") (class "Default")
      (node (ref "R5") (pin "1") (pinfunction "1_1") (pintype "passive"))
      (node (ref "VT1") (pin "5") (pinfunction "G_5") (pintype "passive"))
      (node (ref "VT1") (pin "6") (pinfunction "К_6") (pintype "passive"))
    )
    (net (code "75") (name "Net-(VT1B-Б)") (class "Default")
      (node (ref "R1") (pin "2") (pinfunction "2_2") (pintype "passive"))
      (node (ref "VT1") (pin "2") (pinfunction "Б_2") (pintype "passive"))
    )
    (net (code "76") (name "Net-(XS1-CLK)") (class "Default")
      (node (ref "R7") (pin "1") (pinfunction "1_1") (pintype "passive"))
      (node (ref "XS1") (pin "5") (pinfunction "CLK_5") (pintype "input"))
    )
    (net (code "77") (name "VCC3P3") (class "Default")
      (node (ref "A1") (pin "8") (pinfunction "VCC3P3_8") (pintype "power_in"))
      (node (ref "A1") (pin "9") (pinfunction "VCC3P3_9") (pintype "power_in"))
      (node (ref "C1") (pin "1") (pinfunction "1_1") (pintype "passive"))
      (node (ref "C3") (pin "1") (pinfunction "1_1") (pintype "passive"))
      (node (ref "C4") (pin "2") (pinfunction "2_2") (pintype "passive"))
      (node (ref "C5") (pin "2") (pinfunction "2_2") (pintype "passive"))
      (node (ref "HG1") (pin "11") (pinfunction "BS1_11") (pintype "input"))
      (node (ref "HG1") (pin "6") (pinfunction "VBAT_6") (pintype "power_in"))
      (node (ref "HG1") (pin "9") (pinfunction "VDD_9") (pintype "power_in"))
      (node (ref "HL1") (pin "1") (pinfunction "А_1") (pintype "passive"))
      (node (ref "HL2") (pin "2") (pinfunction "2_2") (pintype "passive"))
      (node (ref "R11") (pin "1") (pinfunction "1_1") (pintype "passive"))
      (node (ref "R12") (pin "1") (pinfunction "1_1") (pintype "passive"))
      (node (ref "R13") (pin "2") (pinfunction "2_2") (pintype "passive"))
      (node (ref "R21") (pin "5") (pintype "passive"))
      (node (ref "R21") (pin "6") (pintype "passive"))
      (node (ref "R21") (pin "7") (pintype "passive"))
      (node (ref "R21") (pin "8") (pintype "passive"))
      (node (ref "R22") (pin "2") (pinfunction "2_2") (pintype "passive"))
      (node (ref "R5") (pin "2") (pinfunction "2_2") (pintype "passive"))
      (node (ref "R6") (pin "2") (pinfunction "2_2") (pintype "passive"))
      (node (ref "R8") (pin "1") (pintype "passive"))
      (node (ref "R8") (pin "2") (pintype "passive"))
      (node (ref "R8") (pin "3") (pintype "passive"))
      (node (ref "R8") (pin "4") (pintype "passive"))
      (node (ref "R9") (pin "1") (pintype "passive"))
      (node (ref "R9") (pin "2") (pintype "passive"))
      (node (ref "R9") (pin "3") (pintype "passive"))
      (node (ref "R9") (pin "4") (pintype "passive"))
      (node (ref "SB1") (pin "1") (pintype "passive"))
      (node (ref "VT1") (pin "4") (pinfunction "S_4") (pintype "passive"))
      (node (ref "XS1") (pin "4") (pinfunction "VDD_4") (pintype "power_in"))
    )
    (net (code "78") (name "VCC_FLASH") (class "Default")
      (node (ref "A1") (pin "32") (pinfunction "VDD_FLASH_32") (pintype "power_in"))
      (node (ref "R14") (pin "2") (pinfunction "2_2") (pintype "passive"))
      (node (ref "R6") (pin "1") (pinfunction "1_1") (pintype "passive"))
      (node (ref "VT1") (pin "3") (pinfunction "D_3") (pintype "passive"))
    )
    (net (code "79") (name "unconnected-(HG1A-NC-Pad7)") (class "Default")
      (node (ref "HG1") (pin "7") (pinfunction "NC_7") (pintype "passive"))
    )
    (net (code "80") (name "unconnected-(R9-Pad5)") (class "Default")
      (node (ref "R9") (pin "5") (pintype "passive"))
    )
  )
)
